# w10-output.net
KiCad netlist of a schematic drawn in EAGLE
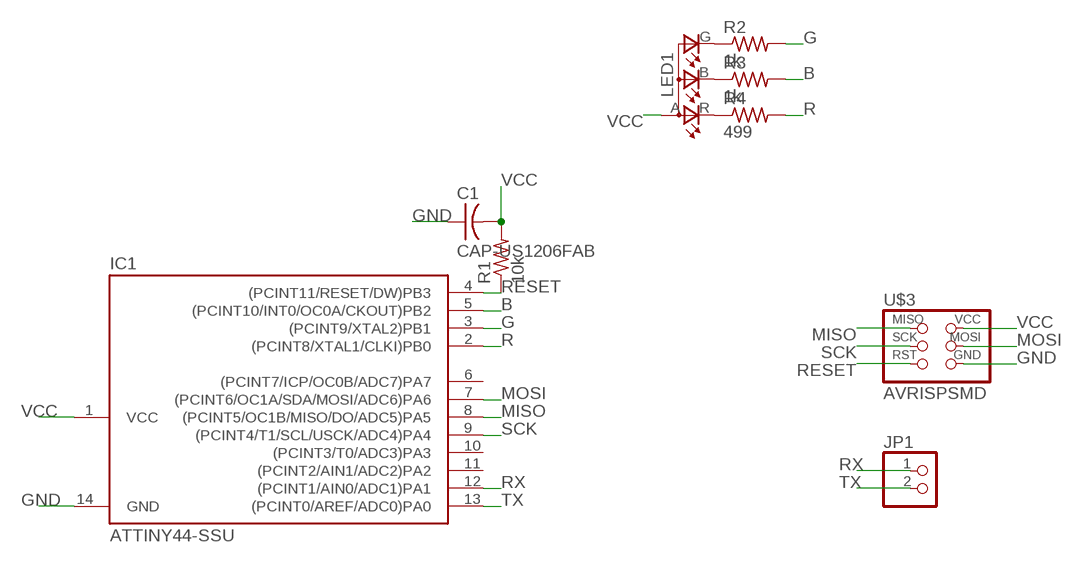
[diagram p0: schematic, sheet 1]

(export (version "E")
  (design (tool "Eeschema 10.0.6"))
  (components
    (comp (ref "C1")
      (value "CAP-US1206FAB")
      (footprint "eagle-import:C1206FAB")
      (libsource (lib "eagle-import") (part "CAP-US1206FAB"))
    )
    (comp (ref "IC1")
      (value "ATTINY44-SSU")
      (footprint "eagle-import:SOIC14")
      (libsource (lib "eagle-import") (part "ATTINY44-SSU"))
    )
    (comp (ref "JP1")
      (value "PINHD-1X2")
      (footprint "eagle-import:1X02")
      (libsource (lib "eagle-import") (part "PINHD-1X2"))
    )
    (comp (ref "LED1")
      (value "LEDRGBOLD")
      (footprint "eagle-import:P-LCC-4-3")
      (libsource (lib "eagle-import") (part "LEDRGBOLD"))
    )
    (comp (ref "R1")
      (value "10k")
      (footprint "eagle-import:R1206FAB")
      (libsource (lib "eagle-import") (part "RES-US1206FAB"))
    )
    (comp (ref "R2")
      (value "1k")
      (footprint "eagle-import:R1206FAB")
      (libsource (lib "eagle-import") (part "RES-US1206FAB"))
    )
    (comp (ref "R3")
      (value "1k")
      (footprint "eagle-import:R1206FAB")
      (libsource (lib "eagle-import") (part "RES-US1206FAB"))
    )
    (comp (ref "R4")
      (value "499")
      (footprint "eagle-import:R1206FAB")
      (libsource (lib "eagle-import") (part "RES-US1206FAB"))
    )
    (comp (ref "U$3")
      (value "AVRISPSMD")
      (footprint "eagle-import:2X03SMD")
      (libsource (lib "eagle-import") (part "AVRISPSMD"))
    )
  )
  (nets
    (net (code "1") (name "/B") (class "Default")
      (node (ref "IC1") (pin "5") (pinfunction "(PCINT10/INT0/OC0A/CKOUT)PB2_5") (pintype "bidirectional"))
      (node (ref "R3") (pin "2") (pinfunction "2_2") (pintype "passive"))
    )
    (net (code "2") (name "/G") (class "Default")
      (node (ref "IC1") (pin "3") (pinfunction "(PCINT9/XTAL2)PB1_3") (pintype "bidirectional"))
      (node (ref "R2") (pin "2") (pinfunction "2_2") (pintype "passive"))
    )
    (net (code "3") (name "/GND") (class "Default")
      (node (ref "C1") (pin "1") (pinfunction "1_1") (pintype "passive"))
      (node (ref "IC1") (pin "14") (pinfunction "GND_14") (pintype "power_in"))
      (node (ref "U$3") (pin "6") (pinfunction "GND_6") (pintype "passive"))
    )
    (net (code "4") (name "/MISO") (class "Default")
      (node (ref "IC1") (pin "8") (pinfunction "(PCINT5/OC1B/MISO/DO/ADC5)PA5_8") (pintype "bidirectional"))
      (node (ref "U$3") (pin "1") (pinfunction "MISO_1") (pintype "passive"))
    )
    (net (code "5") (name "/MOSI") (class "Default")
      (node (ref "IC1") (pin "7") (pinfunction "(PCINT6/OC1A/SDA/MOSI/ADC6)PA6_7") (pintype "bidirectional"))
      (node (ref "U$3") (pin "4") (pinfunction "MOSI_4") (pintype "passive"))
    )
    (net (code "6") (name "/R") (class "Default")
      (node (ref "IC1") (pin "2") (pinfunction "(PCINT8/XTAL1/CLKI)PB0_2") (pintype "bidirectional"))
      (node (ref "R4") (pin "2") (pinfunction "2_2") (pintype "passive"))
    )
    (net (code "7") (name "/RESET") (class "Default")
      (node (ref "IC1") (pin "4") (pinfunction "(PCINT11/RESET/DW)PB3_4") (pintype "bidirectional"))
      (node (ref "R1") (pin "1") (pinfunction "1_1") (pintype "passive"))
      (node (ref "U$3") (pin "5") (pinfunction "RST_5") (pintype "passive"))
    )
    (net (code "8") (name "/RX") (class "Default")
      (node (ref "IC1") (pin "12") (pinfunction "(PCINT1/AIN0/ADC1)PA1_12") (pintype "bidirectional"))
      (node (ref "JP1") (pin "1") (pinfunction "1_1") (pintype "passive"))
    )
    (net (code "9") (name "/SCK") (class "Default")
      (node (ref "IC1") (pin "9") (pinfunction "(PCINT4/T1/SCL/USCK/ADC4)PA4_9") (pintype "bidirectional"))
      (node (ref "U$3") (pin "3") (pinfunction "SCK_3") (pintype "passive"))
    )
    (net (code "10") (name "/TX") (class "Default")
      (node (ref "IC1") (pin "13") (pinfunction "(PCINT0/AREF/ADC0)PA0_13") (pintype "bidirectional"))
      (node (ref "JP1") (pin "2") (pinfunction "2_2") (pintype "passive"))
    )
    (net (code "11") (name "/VCC") (class "Default")
      (node (ref "C1") (pin "2") (pinfunction "2_2") (pintype "passive"))
      (node (ref "IC1") (pin "1") (pinfunction "VCC_1") (pintype "power_in"))
      (node (ref "LED1") (pin "A") (pinfunction "A2_A") (pintype "passive"))
      (node (ref "R1") (pin "2") (pinfunction "2_2") (pintype "passive"))
      (node (ref "U$3") (pin "2") (pinfunction "VCC_2") (pintype "passive"))
    )
    (net (code "12") (name "Net-(LED1-CBLUE)") (class "Default")
      (node (ref "LED1") (pin "B") (pinfunction "CBLUE_B") (pintype "passive"))
      (node (ref "R3") (pin "1") (pinfunction "1_1") (pintype "passive"))
    )
    (net (code "13") (name "Net-(LED1-CGREEN)") (class "Default")
      (node (ref "LED1") (pin "G") (pinfunction "CGREEN_G") (pintype "passive"))
      (node (ref "R2") (pin "1") (pinfunction "1_1") (pintype "passive"))
    )
    (net (code "14") (name "Net-(LED1-CRED)") (class "Default")
      (node (ref "LED1") (pin "R") (pinfunction "CRED_R") (pintype "passive"))
      (node (ref "R4") (pin "1") (pinfunction "1_1") (pintype "passive"))
    )
    (net (code "15") (name "unconnected-(IC1-(PCINT2{slash}AIN1{slash}ADC2)PA2-Pad11)") (class "Default")
      (node (ref "IC1") (pin "11") (pinfunction "(PCINT2/AIN1/ADC2)PA2_11") (pintype "bidirectional"))
    )
    (net (code "16") (name "unconnected-(IC1-(PCINT3{slash}T0{slash}ADC3)PA3-Pad10)") (class "Default")
      (node (ref "IC1") (pin "10") (pinfunction "(PCINT3/T0/ADC3)PA3_10") (pintype "bidirectional"))
    )
    (net (code "17") (name "unconnected-(IC1-(PCINT7{slash}ICP{slash}OC0B{slash}ADC7)PA7-Pad6)") (class "Default")
      (node (ref "IC1") (pin "6") (pinfunction "(PCINT7/ICP/OC0B/ADC7)PA7_6") (pintype "bidirectional"))
    )
  )
)
